# AS3364_waveform_VCA_0402_DIL_v1_0.net
KiCad netlist of a schematic drawn in EAGLE
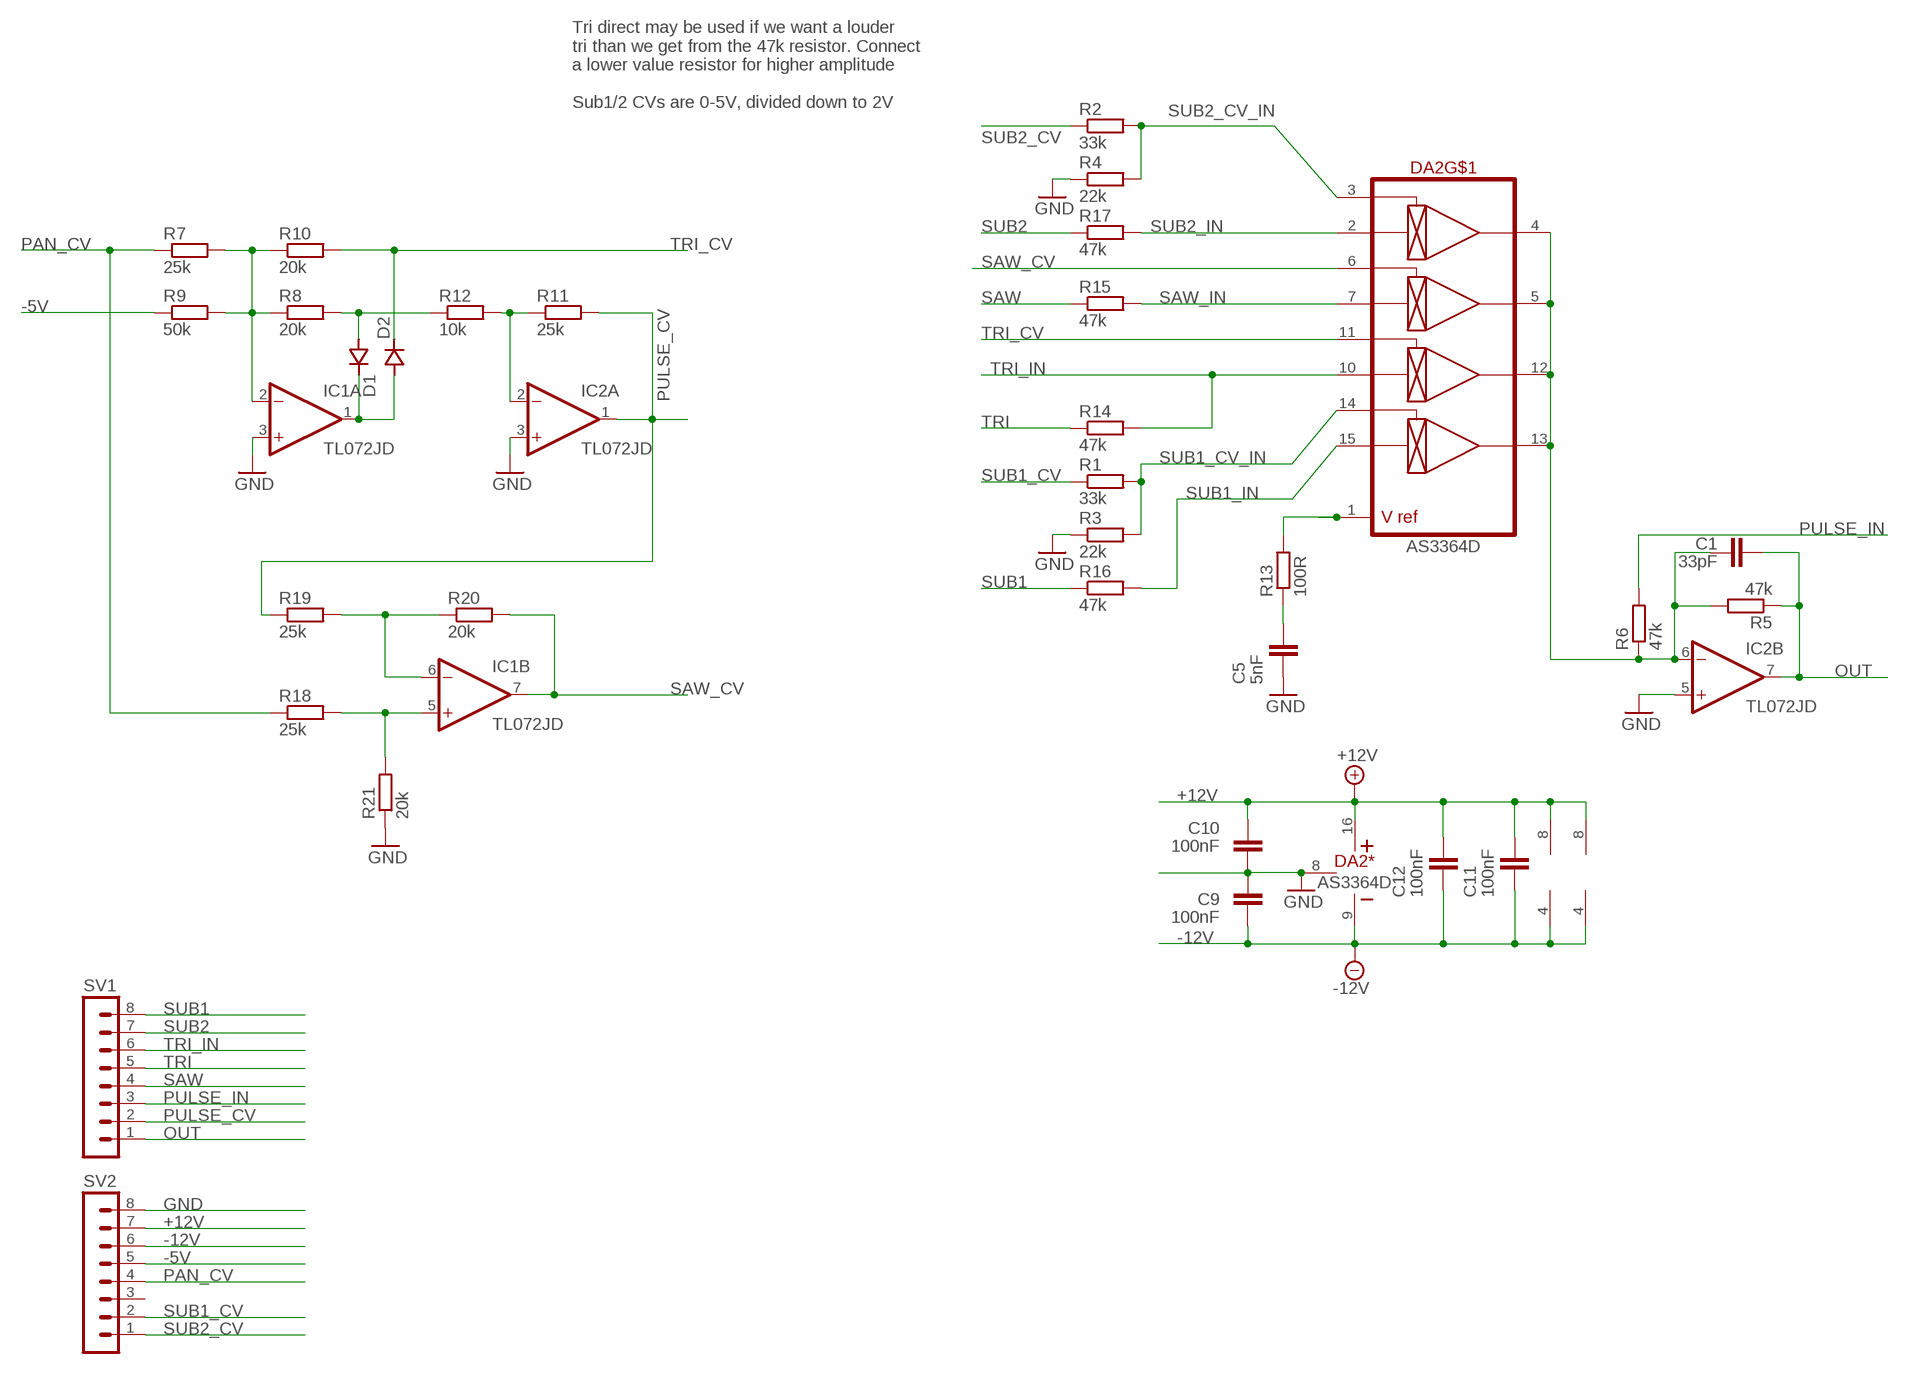
[diagram p0: schematic, sheet 1]

(export (version "E")
  (design (tool "Eeschema 10.0.6"))
  (components
    (comp (ref "C1")
      (value "33pF")
      (footprint "eagle-import:C0402")
      (libsource (lib "eagle-import") (part "C-EUC0402"))
    )
    (comp (ref "C5")
      (value "5nF")
      (footprint "eagle-import:C0402")
      (libsource (lib "eagle-import") (part "C-EUC0402"))
    )
    (comp (ref "C9")
      (value "100nF")
      (footprint "eagle-import:C0402")
      (libsource (lib "eagle-import") (part "C-EUC0402"))
    )
    (comp (ref "C10")
      (value "100nF")
      (footprint "eagle-import:C0402")
      (libsource (lib "eagle-import") (part "C-EUC0402"))
    )
    (comp (ref "C11")
      (value "100nF")
      (footprint "eagle-import:C0402")
      (libsource (lib "eagle-import") (part "C-EUC0402"))
    )
    (comp (ref "C12")
      (value "100nF")
      (footprint "eagle-import:C0402")
      (libsource (lib "eagle-import") (part "C-EUC0402"))
    )
    (comp (ref "D1")
      (value "DIODESOD323")
      (footprint "eagle-import:SOD323J")
      (fields (field (name "MPN") "CDSOD323-T05C"))
      (libsource (lib "eagle-import") (part "DIODESOD323"))
    )
    (comp (ref "D2")
      (value "DIODESOD323")
      (footprint "eagle-import:SOD323J")
      (fields (field (name "MPN") "CDSOD323-T05C"))
      (libsource (lib "eagle-import") (part "DIODESOD323"))
    )
    (comp (ref "DA2")
      (value "AS3364D")
      (footprint "eagle-import:DIL16J")
      (libsource (lib "eagle-import") (part "AS3364D"))
    )
    (comp (ref "IC1")
      (value "TL072JD")
      (footprint "eagle-import:SO08J")
      (libsource (lib "eagle-import") (part "TL072JD"))
    )
    (comp (ref "IC2")
      (value "TL072JD")
      (footprint "eagle-import:SO08J")
      (libsource (lib "eagle-import") (part "TL072JD"))
    )
    (comp (ref "R1")
      (value "33k")
      (footprint "eagle-import:R0402")
      (libsource (lib "eagle-import") (part "R-EU_R0402"))
    )
    (comp (ref "R2")
      (value "33k")
      (footprint "eagle-import:R0402")
      (libsource (lib "eagle-import") (part "R-EU_R0402"))
    )
    (comp (ref "R3")
      (value "22k")
      (footprint "eagle-import:R0402")
      (libsource (lib "eagle-import") (part "R-EU_R0402"))
    )
    (comp (ref "R4")
      (value "22k")
      (footprint "eagle-import:R0402")
      (libsource (lib "eagle-import") (part "R-EU_R0402"))
    )
    (comp (ref "R5")
      (value "47k")
      (footprint "eagle-import:R0402")
      (libsource (lib "eagle-import") (part "R-EU_R0402"))
    )
    (comp (ref "R6")
      (value "47k")
      (footprint "eagle-import:R0402")
      (libsource (lib "eagle-import") (part "R-EU_R0402"))
    )
    (comp (ref "R7")
      (value "25k")
      (footprint "eagle-import:R0402")
      (libsource (lib "eagle-import") (part "R-EU_R0402"))
    )
    (comp (ref "R8")
      (value "20k")
      (footprint "eagle-import:R0402")
      (libsource (lib "eagle-import") (part "R-EU_R0402"))
    )
    (comp (ref "R9")
      (value "50k")
      (footprint "eagle-import:R0402")
      (libsource (lib "eagle-import") (part "R-EU_R0402"))
    )
    (comp (ref "R10")
      (value "20k")
      (footprint "eagle-import:R0402")
      (libsource (lib "eagle-import") (part "R-EU_R0402"))
    )
    (comp (ref "R11")
      (value "25k")
      (footprint "eagle-import:R0402")
      (libsource (lib "eagle-import") (part "R-EU_R0402"))
    )
    (comp (ref "R12")
      (value "10k")
      (footprint "eagle-import:R0402")
      (libsource (lib "eagle-import") (part "R-EU_R0402"))
    )
    (comp (ref "R13")
      (value "100R")
      (footprint "eagle-import:R0402")
      (libsource (lib "eagle-import") (part "R-EU_R0402"))
    )
    (comp (ref "R14")
      (value "47k")
      (footprint "eagle-import:R0402")
      (libsource (lib "eagle-import") (part "R-EU_R0402"))
    )
    (comp (ref "R15")
      (value "47k")
      (footprint "eagle-import:R0402")
      (libsource (lib "eagle-import") (part "R-EU_R0402"))
    )
    (comp (ref "R16")
      (value "47k")
      (footprint "eagle-import:R0402")
      (libsource (lib "eagle-import") (part "R-EU_R0402"))
    )
    (comp (ref "R17")
      (value "47k")
      (footprint "eagle-import:R0402")
      (libsource (lib "eagle-import") (part "R-EU_R0402"))
    )
    (comp (ref "R18")
      (value "25k")
      (footprint "eagle-import:R0402")
      (libsource (lib "eagle-import") (part "R-EU_R0402"))
    )
    (comp (ref "R19")
      (value "25k")
      (footprint "eagle-import:R0402")
      (libsource (lib "eagle-import") (part "R-EU_R0402"))
    )
    (comp (ref "R20")
      (value "20k")
      (footprint "eagle-import:R0402")
      (libsource (lib "eagle-import") (part "R-EU_R0402"))
    )
    (comp (ref "R21")
      (value "20k")
      (footprint "eagle-import:R0402")
      (libsource (lib "eagle-import") (part "R-EU_R0402"))
    )
    (comp (ref "SV1")
      (value "MA08-1JP")
      (footprint "eagle-import:SIP-PIN08-1J")
      (libsource (lib "eagle-import") (part "MA08-1JP"))
    )
    (comp (ref "SV2")
      (value "MA08-1JP")
      (footprint "eagle-import:SIP-PIN08-1J")
      (libsource (lib "eagle-import") (part "MA08-1JP"))
    )
  )
  (nets
    (net (code "1") (name "+12V") (class "Default")
      (node (ref "C10") (pin "2") (pinfunction "2_2") (pintype "passive"))
      (node (ref "C11") (pin "2") (pinfunction "2_2") (pintype "passive"))
      (node (ref "C12") (pin "2") (pinfunction "2_2") (pintype "passive"))
      (node (ref "DA2") (pin "16") (pinfunction "V+_16") (pintype "power_in"))
      (node (ref "IC1") (pin "8") (pinfunction "V+_8") (pintype "power_in"))
      (node (ref "IC2") (pin "8") (pinfunction "V+_8") (pintype "power_in"))
      (node (ref "SV2") (pin "7") (pinfunction "7_7") (pintype "passive"))
    )
    (net (code "2") (name "-12V") (class "Default")
      (node (ref "C11") (pin "1") (pinfunction "1_1") (pintype "passive"))
      (node (ref "C12") (pin "1") (pinfunction "1_1") (pintype "passive"))
      (node (ref "C9") (pin "1") (pinfunction "1_1") (pintype "passive"))
      (node (ref "DA2") (pin "9") (pinfunction "V-_9") (pintype "power_in"))
      (node (ref "IC1") (pin "4") (pinfunction "V-_4") (pintype "power_in"))
      (node (ref "IC2") (pin "4") (pinfunction "V-_4") (pintype "power_in"))
      (node (ref "SV2") (pin "6") (pinfunction "6_6") (pintype "passive"))
    )
    (net (code "3") (name "/-5V") (class "Default")
      (node (ref "R9") (pin "1") (pinfunction "1_1") (pintype "passive"))
      (node (ref "SV2") (pin "5") (pinfunction "5_5") (pintype "passive"))
    )
    (net (code "4") (name "/OUT") (class "Default")
      (node (ref "C1") (pin "1") (pinfunction "1_1") (pintype "passive"))
      (node (ref "IC2") (pin "7") (pinfunction "OUT_7") (pintype "output"))
      (node (ref "R5") (pin "1") (pinfunction "1_1") (pintype "passive"))
      (node (ref "SV1") (pin "1") (pinfunction "1_1") (pintype "passive"))
    )
    (net (code "5") (name "/PAN_CV") (class "Default")
      (node (ref "R18") (pin "1") (pinfunction "1_1") (pintype "passive"))
      (node (ref "R7") (pin "1") (pinfunction "1_1") (pintype "passive"))
      (node (ref "SV2") (pin "4") (pinfunction "4_4") (pintype "passive"))
    )
    (net (code "6") (name "/PULSE_CV") (class "Default")
      (node (ref "IC2") (pin "1") (pinfunction "OUT_1") (pintype "output"))
      (node (ref "R11") (pin "2") (pinfunction "2_2") (pintype "passive"))
      (node (ref "R19") (pin "1") (pinfunction "1_1") (pintype "passive"))
      (node (ref "SV1") (pin "2") (pinfunction "2_2") (pintype "passive"))
    )
    (net (code "7") (name "/PULSE_IN") (class "Default")
      (node (ref "R6") (pin "2") (pinfunction "2_2") (pintype "passive"))
      (node (ref "SV1") (pin "3") (pinfunction "3_3") (pintype "passive"))
    )
    (net (code "8") (name "/SAW") (class "Default")
      (node (ref "R15") (pin "1") (pinfunction "1_1") (pintype "passive"))
      (node (ref "SV1") (pin "4") (pinfunction "4_4") (pintype "passive"))
    )
    (net (code "9") (name "/SAW_CV") (class "Default")
      (node (ref "DA2") (pin "6") (pinfunction "CV2_6") (pintype "input"))
      (node (ref "IC1") (pin "7") (pinfunction "OUT_7") (pintype "output"))
      (node (ref "R20") (pin "2") (pinfunction "2_2") (pintype "passive"))
    )
    (net (code "10") (name "/SAW_IN") (class "Default")
      (node (ref "DA2") (pin "7") (pinfunction "IN2_7") (pintype "input"))
      (node (ref "R15") (pin "2") (pinfunction "2_2") (pintype "passive"))
    )
    (net (code "11") (name "/SUB1") (class "Default")
      (node (ref "R16") (pin "1") (pinfunction "1_1") (pintype "passive"))
      (node (ref "SV1") (pin "8") (pinfunction "8_8") (pintype "passive"))
    )
    (net (code "12") (name "/SUB1_CV") (class "Default")
      (node (ref "R1") (pin "1") (pinfunction "1_1") (pintype "passive"))
      (node (ref "SV2") (pin "2") (pinfunction "2_2") (pintype "passive"))
    )
    (net (code "13") (name "/SUB1_CV_IN") (class "Default")
      (node (ref "DA2") (pin "14") (pinfunction "CV4_14") (pintype "input"))
      (node (ref "R1") (pin "2") (pinfunction "2_2") (pintype "passive"))
      (node (ref "R3") (pin "2") (pinfunction "2_2") (pintype "passive"))
    )
    (net (code "14") (name "/SUB1_IN") (class "Default")
      (node (ref "DA2") (pin "15") (pinfunction "IN4_15") (pintype "input"))
      (node (ref "R16") (pin "2") (pinfunction "2_2") (pintype "passive"))
    )
    (net (code "15") (name "/SUB2") (class "Default")
      (node (ref "R17") (pin "1") (pinfunction "1_1") (pintype "passive"))
      (node (ref "SV1") (pin "7") (pinfunction "7_7") (pintype "passive"))
    )
    (net (code "16") (name "/SUB2_CV") (class "Default")
      (node (ref "R2") (pin "1") (pinfunction "1_1") (pintype "passive"))
      (node (ref "SV2") (pin "1") (pinfunction "1_1") (pintype "passive"))
    )
    (net (code "17") (name "/SUB2_CV_IN") (class "Default")
      (node (ref "DA2") (pin "3") (pinfunction "CV1_3") (pintype "input"))
      (node (ref "R2") (pin "2") (pinfunction "2_2") (pintype "passive"))
      (node (ref "R4") (pin "2") (pinfunction "2_2") (pintype "passive"))
    )
    (net (code "18") (name "/SUB2_IN") (class "Default")
      (node (ref "DA2") (pin "2") (pinfunction "IN1_2") (pintype "input"))
      (node (ref "R17") (pin "2") (pinfunction "2_2") (pintype "passive"))
    )
    (net (code "19") (name "/TRI") (class "Default")
      (node (ref "R14") (pin "1") (pinfunction "1_1") (pintype "passive"))
      (node (ref "SV1") (pin "5") (pinfunction "5_5") (pintype "passive"))
    )
    (net (code "20") (name "/TRI_CV") (class "Default")
      (node (ref "D2") (pin "1") (pinfunction "C_1") (pintype "passive"))
      (node (ref "DA2") (pin "11") (pinfunction "CV3_11") (pintype "input"))
      (node (ref "R10") (pin "2") (pinfunction "2_2") (pintype "passive"))
    )
    (net (code "21") (name "/TRI_IN") (class "Default")
      (node (ref "DA2") (pin "10") (pinfunction "IN3_10") (pintype "input"))
      (node (ref "R14") (pin "2") (pinfunction "2_2") (pintype "passive"))
      (node (ref "SV1") (pin "6") (pinfunction "6_6") (pintype "passive"))
    )
    (net (code "22") (name "GND") (class "Default")
      (node (ref "C10") (pin "1") (pinfunction "1_1") (pintype "passive"))
      (node (ref "C5") (pin "1") (pinfunction "1_1") (pintype "passive"))
      (node (ref "C9") (pin "2") (pinfunction "2_2") (pintype "passive"))
      (node (ref "DA2") (pin "8") (pinfunction "GND_8") (pintype "power_in"))
      (node (ref "IC1") (pin "3") (pinfunction "+IN_3") (pintype "input"))
      (node (ref "IC2") (pin "3") (pinfunction "+IN_3") (pintype "input"))
      (node (ref "IC2") (pin "5") (pinfunction "+IN_5") (pintype "input"))
      (node (ref "R21") (pin "1") (pinfunction "1_1") (pintype "passive"))
      (node (ref "R3") (pin "1") (pinfunction "1_1") (pintype "passive"))
      (node (ref "R4") (pin "1") (pinfunction "1_1") (pintype "passive"))
      (node (ref "SV2") (pin "8") (pinfunction "8_8") (pintype "passive"))
    )
    (net (code "23") (name "Net-(C5-Pad2)") (class "Default")
      (node (ref "C5") (pin "2") (pinfunction "2_2") (pintype "passive"))
      (node (ref "R13") (pin "1") (pinfunction "1_1") (pintype "passive"))
    )
    (net (code "24") (name "Net-(D1-A)") (class "Default")
      (node (ref "D1") (pin "2") (pinfunction "A_2") (pintype "passive"))
      (node (ref "R12") (pin "1") (pinfunction "1_1") (pintype "passive"))
      (node (ref "R8") (pin "2") (pinfunction "2_2") (pintype "passive"))
    )
    (net (code "25") (name "Net-(D1-C)") (class "Default")
      (node (ref "D1") (pin "1") (pinfunction "C_1") (pintype "passive"))
      (node (ref "D2") (pin "2") (pinfunction "A_2") (pintype "passive"))
      (node (ref "IC1") (pin "1") (pinfunction "OUT_1") (pintype "output"))
    )
    (net (code "26") (name "Net-(DA2B-OUT1)") (class "Default")
      (node (ref "C1") (pin "2") (pinfunction "2_2") (pintype "passive"))
      (node (ref "DA2") (pin "12") (pinfunction "OUT3_12") (pintype "output"))
      (node (ref "DA2") (pin "13") (pinfunction "OUT4_13") (pintype "output"))
      (node (ref "DA2") (pin "4") (pinfunction "OUT1_4") (pintype "output"))
      (node (ref "DA2") (pin "5") (pinfunction "OUT2_5") (pintype "output"))
      (node (ref "IC2") (pin "6") (pinfunction "-IN_6") (pintype "input"))
      (node (ref "R5") (pin "2") (pinfunction "2_2") (pintype "passive"))
      (node (ref "R6") (pin "1") (pinfunction "1_1") (pintype "passive"))
    )
    (net (code "27") (name "Net-(DA2B-VREF)") (class "Default")
      (node (ref "DA2") (pin "1") (pinfunction "VREF_1") (pintype "output"))
      (node (ref "R13") (pin "2") (pinfunction "2_2") (pintype "passive"))
    )
    (net (code "28") (name "Net-(IC1A--IN)") (class "Default")
      (node (ref "IC1") (pin "2") (pinfunction "-IN_2") (pintype "input"))
      (node (ref "R10") (pin "1") (pinfunction "1_1") (pintype "passive"))
      (node (ref "R7") (pin "2") (pinfunction "2_2") (pintype "passive"))
      (node (ref "R8") (pin "1") (pinfunction "1_1") (pintype "passive"))
      (node (ref "R9") (pin "2") (pinfunction "2_2") (pintype "passive"))
    )
    (net (code "29") (name "Net-(IC1B-+IN)") (class "Default")
      (node (ref "IC1") (pin "5") (pinfunction "+IN_5") (pintype "input"))
      (node (ref "R18") (pin "2") (pinfunction "2_2") (pintype "passive"))
      (node (ref "R21") (pin "2") (pinfunction "2_2") (pintype "passive"))
    )
    (net (code "30") (name "Net-(IC1B--IN)") (class "Default")
      (node (ref "IC1") (pin "6") (pinfunction "-IN_6") (pintype "input"))
      (node (ref "R19") (pin "2") (pinfunction "2_2") (pintype "passive"))
      (node (ref "R20") (pin "1") (pinfunction "1_1") (pintype "passive"))
    )
    (net (code "31") (name "Net-(IC2A--IN)") (class "Default")
      (node (ref "IC2") (pin "2") (pinfunction "-IN_2") (pintype "input"))
      (node (ref "R11") (pin "1") (pinfunction "1_1") (pintype "passive"))
      (node (ref "R12") (pin "2") (pinfunction "2_2") (pintype "passive"))
    )
    (net (code "32") (name "unconnected-(SV2-Pad3)") (class "Default")
      (node (ref "SV2") (pin "3") (pinfunction "3_3") (pintype "passive"))
    )
  )
)
